# BeagleQ-v31.net
KiCad netlist of a schematic drawn in EAGLE
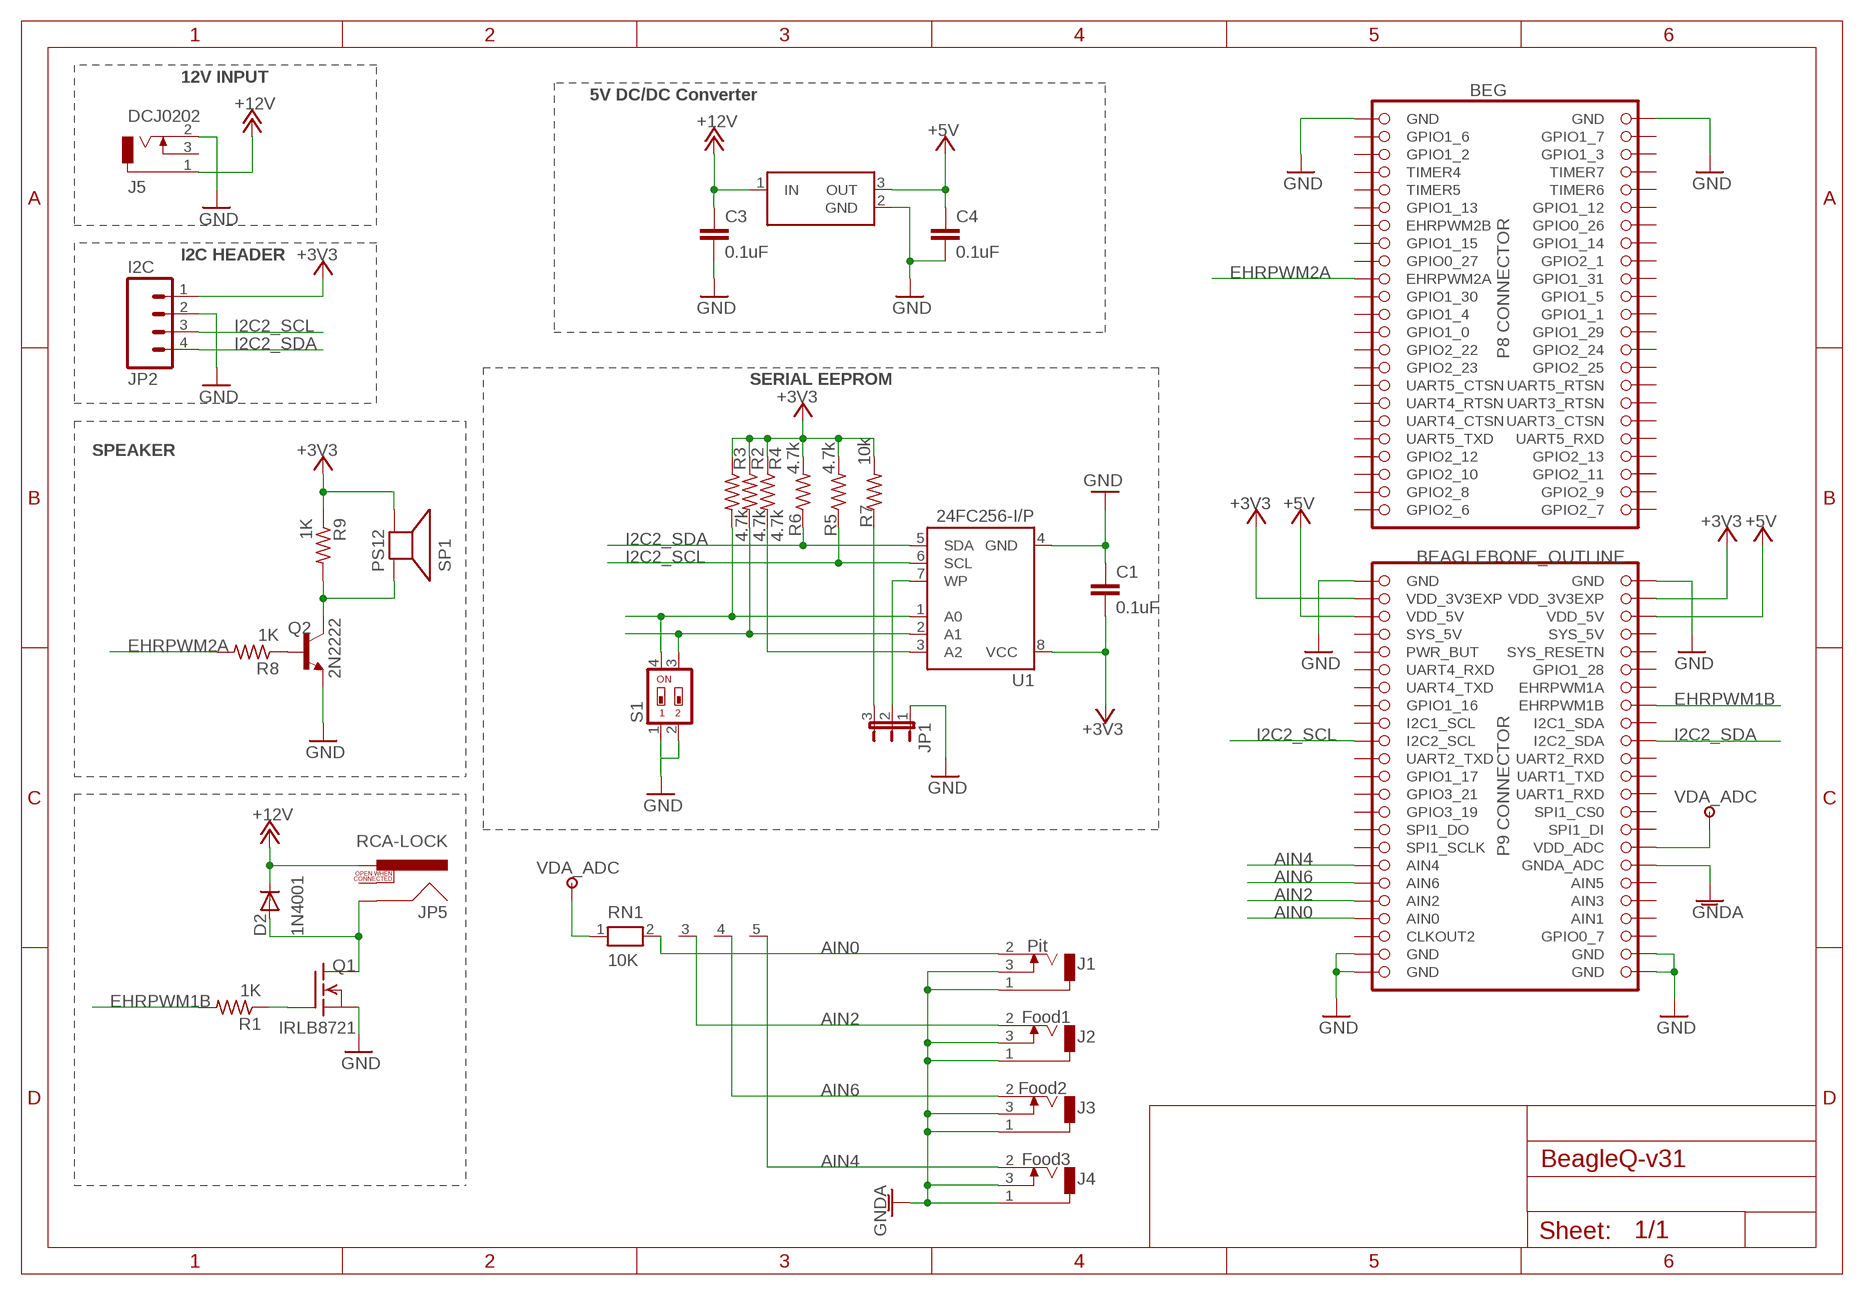
[diagram p0: schematic, sheet 1]

(export (version "E")
  (design (tool "Eeschema 10.0.6"))
  (components
    (comp (ref "BEG")
      (value "BEAGLEBONE_OUTLINE")
      (footprint "eagle-import:BEAGLEBONE_SHIELD")
      (libsource (lib "eagle-import") (part "BEAGLEBONE_OUTLINE"))
    )
    (comp (ref "C1")
      (value "0.1uF")
      (footprint "eagle-import:C2.5-2")
      (libsource (lib "eagle-import") (part "C2.5/2"))
    )
    (comp (ref "C3")
      (value "0.1uF")
      (footprint "eagle-import:C2.5-2")
      (libsource (lib "eagle-import") (part "C2.5/2"))
    )
    (comp (ref "C4")
      (value "0.1uF")
      (footprint "eagle-import:C2.5-2")
      (libsource (lib "eagle-import") (part "C2.5/2"))
    )
    (comp (ref "D2")
      (value "1N4001")
      (footprint "eagle-import:DO41-10")
      (libsource (lib "eagle-import") (part "1N4004"))
    )
    (comp (ref "J1")
      (value "Pit")
      (footprint "eagle-import:MJ-2508N")
      (libsource (lib "eagle-import") (part "MJ-2508N"))
    )
    (comp (ref "J2")
      (value "Food1")
      (footprint "eagle-import:MJ-2508N")
      (libsource (lib "eagle-import") (part "MJ-2508N"))
    )
    (comp (ref "J3")
      (value "Food2")
      (footprint "eagle-import:MJ-2508N")
      (libsource (lib "eagle-import") (part "MJ-2508N"))
    )
    (comp (ref "J4")
      (value "Food3")
      (footprint "eagle-import:MJ-2508N")
      (libsource (lib "eagle-import") (part "MJ-2508N"))
    )
    (comp (ref "J5")
      (value "DCJ0202")
      (footprint "eagle-import:DCJ0202")
      (libsource (lib "eagle-import") (part "DCJ0202"))
    )
    (comp (ref "JP1")
      (value "WP")
      (footprint "eagle-import:JP2")
      (libsource (lib "eagle-import") (part "JP2E"))
    )
    (comp (ref "JP2")
      (value "I2C")
      (footprint "eagle-import:1X04")
      (libsource (lib "eagle-import") (part "M04PTH"))
    )
    (comp (ref "JP5")
      (value "RCA-LOCK")
      (footprint "eagle-import:RCA_LOCK")
      (libsource (lib "eagle-import") (part "RCA-LOCK"))
    )
    (comp (ref "Q1")
      (value "IRLB8721")
      (footprint "eagle-import:TO220")
      (libsource (lib "eagle-import") (part "BUZ10"))
    )
    (comp (ref "Q2")
      (value "2N2222")
      (footprint "eagle-import:TO-92")
      (libsource (lib "eagle-import") (part "2N2222"))
    )
    (comp (ref "R1")
      (value "1K")
      (footprint "eagle-import:0207_10")
      (libsource (lib "eagle-import") (part "R-US_0207/10"))
    )
    (comp (ref "R2")
      (value "4.7k")
      (footprint "eagle-import:0207_10")
      (libsource (lib "eagle-import") (part "resistor_R-US_0207/10"))
    )
    (comp (ref "R3")
      (value "4.7k")
      (footprint "eagle-import:0207_10")
      (libsource (lib "eagle-import") (part "resistor_R-US_0207/10"))
    )
    (comp (ref "R4")
      (value "4.7k")
      (footprint "eagle-import:0207_10")
      (libsource (lib "eagle-import") (part "resistor_R-US_0207/10"))
    )
    (comp (ref "R5")
      (value "4.7k")
      (footprint "eagle-import:0207_10")
      (libsource (lib "eagle-import") (part "resistor_R-US_0207/10"))
    )
    (comp (ref "R6")
      (value "4.7k")
      (footprint "eagle-import:0207_10")
      (libsource (lib "eagle-import") (part "resistor_R-US_0207/10"))
    )
    (comp (ref "R7")
      (value "10k")
      (footprint "eagle-import:0207_10")
      (libsource (lib "eagle-import") (part "resistor_R-US_0207/10"))
    )
    (comp (ref "R8")
      (value "1K")
      (footprint "eagle-import:0207_10")
      (libsource (lib "eagle-import") (part "R-US_0207/10"))
    )
    (comp (ref "R9")
      (value "1K")
      (footprint "eagle-import:0207_10")
      (libsource (lib "eagle-import") (part "R-US_0207/10"))
    )
    (comp (ref "RN1")
      (value "10K")
      (footprint "eagle-import:RN-5")
      (libsource (lib "eagle-import") (part "RN04"))
    )
    (comp (ref "S1")
      (value "SWS002")
      (footprint "eagle-import:SMS-002")
      (libsource (lib "eagle-import") (part "SWS002"))
    )
    (comp (ref "SP1")
      (value "PS12")
      (footprint "eagle-import:PS12")
      (libsource (lib "eagle-import") (part "SPEAKER/PS12"))
    )
    (comp (ref "U1")
      (value "24FC256-I/P")
      (footprint "eagle-import:DIL08")
      (fields (field (name "MPN") "AT24C1024BW-SH-B"))
      (libsource (lib "eagle-import") (part "AT24CP"))
    )
    (comp (ref "U2")
      (value "OKI-78SRHZNTL")
      (footprint "eagle-import:OKI-78SR-HZNTL")
      (libsource (lib "eagle-import") (part "OKI-78SRHZNTL"))
    )
  )
  (nets
    (net (code "1") (name "+3V3") (class "Default")
      (node (ref "BEG") (pin "49") (pinfunction "VDD_3V3EXP_49") (pintype "power_in"))
      (node (ref "BEG") (pin "50") (pinfunction "VDD_3V3EXP_50") (pintype "power_in"))
      (node (ref "C1") (pin "2") (pinfunction "2_2") (pintype "passive"))
      (node (ref "JP2") (pin "1") (pinfunction "1_1") (pintype "passive"))
      (node (ref "R2") (pin "1") (pinfunction "1_1") (pintype "passive"))
      (node (ref "R3") (pin "1") (pinfunction "1_1") (pintype "passive"))
      (node (ref "R4") (pin "1") (pinfunction "1_1") (pintype "passive"))
      (node (ref "R5") (pin "2") (pinfunction "2_2") (pintype "passive"))
      (node (ref "R6") (pin "2") (pinfunction "2_2") (pintype "passive"))
      (node (ref "R7") (pin "2") (pinfunction "2_2") (pintype "passive"))
      (node (ref "R9") (pin "1") (pinfunction "1_1") (pintype "passive"))
      (node (ref "SP1") (pin "P$2") (pinfunction "-_P$2") (pintype "passive"))
      (node (ref "U1") (pin "8") (pinfunction "VCC_8") (pintype "power_in"))
    )
    (net (code "2") (name "+5V") (class "Default")
      (node (ref "BEG") (pin "51") (pinfunction "VDD_5V_51") (pintype "power_in"))
      (node (ref "BEG") (pin "52") (pinfunction "VDD_5V_52") (pintype "power_in"))
      (node (ref "C4") (pin "1") (pinfunction "1_1") (pintype "passive"))
      (node (ref "U2") (pin "3") (pinfunction "OUT_3") (pintype "passive"))
    )
    (net (code "3") (name "+12V") (class "Default")
      (node (ref "C3") (pin "1") (pinfunction "1_1") (pintype "passive"))
      (node (ref "D2") (pin "C") (pinfunction "C_C") (pintype "passive"))
      (node (ref "J5") (pin "1") (pinfunction "1_1") (pintype "passive"))
      (node (ref "JP5") (pin "PIN") (pinfunction "PIN_PIN") (pintype "bidirectional"))
      (node (ref "U2") (pin "1") (pinfunction "IN_1") (pintype "passive"))
    )
    (net (code "4") (name "/AIN0") (class "Default")
      (node (ref "BEG") (pin "85") (pinfunction "AIN0_85") (pintype "power_in"))
      (node (ref "J1") (pin "2") (pinfunction "2_2") (pintype "passive"))
      (node (ref "RN1") (pin "2") (pinfunction "2_2") (pintype "passive"))
    )
    (net (code "5") (name "/AIN2") (class "Default")
      (node (ref "BEG") (pin "83") (pinfunction "AIN2_83") (pintype "passive"))
      (node (ref "J2") (pin "2") (pinfunction "2_2") (pintype "passive"))
      (node (ref "RN1") (pin "3") (pinfunction "3_3") (pintype "passive"))
    )
    (net (code "6") (name "/AIN4") (class "Default")
      (node (ref "BEG") (pin "79") (pinfunction "AIN4_79") (pintype "passive"))
      (node (ref "J4") (pin "2") (pinfunction "2_2") (pintype "passive"))
      (node (ref "RN1") (pin "5") (pinfunction "5_5") (pintype "passive"))
    )
    (net (code "7") (name "/AIN6") (class "Default")
      (node (ref "BEG") (pin "81") (pinfunction "AIN6_81") (pintype "passive"))
      (node (ref "J3") (pin "2") (pinfunction "2_2") (pintype "passive"))
      (node (ref "RN1") (pin "4") (pinfunction "4_4") (pintype "passive"))
    )
    (net (code "8") (name "/EHRPWM1B") (class "Default")
      (node (ref "BEG") (pin "62") (pinfunction "EHRPWM1B_62") (pintype "passive"))
      (node (ref "R1") (pin "2") (pinfunction "2_2") (pintype "passive"))
    )
    (net (code "9") (name "/EHRPWM2A") (class "Default")
      (node (ref "BEG") (pin "19") (pinfunction "EHRPWM2A_19") (pintype "passive"))
      (node (ref "R8") (pin "2") (pinfunction "2_2") (pintype "passive"))
    )
    (net (code "10") (name "/I2C2_SCL") (class "Default")
      (node (ref "BEG") (pin "65") (pinfunction "I2C2_SCL_65") (pintype "passive"))
      (node (ref "JP2") (pin "3") (pinfunction "3_3") (pintype "passive"))
      (node (ref "R5") (pin "1") (pinfunction "1_1") (pintype "passive"))
      (node (ref "U1") (pin "6") (pinfunction "SCL_6") (pintype "bidirectional"))
    )
    (net (code "11") (name "/I2C2_SDA") (class "Default")
      (node (ref "BEG") (pin "66") (pinfunction "I2C2_SDA_66") (pintype "passive"))
      (node (ref "JP2") (pin "4") (pinfunction "4_4") (pintype "passive"))
      (node (ref "R6") (pin "1") (pinfunction "1_1") (pintype "passive"))
      (node (ref "U1") (pin "5") (pinfunction "SDA_5") (pintype "bidirectional"))
    )
    (net (code "12") (name "/SYS_5V") (class "Default")
      (node (ref "BEG") (pin "53") (pinfunction "SYS_5V_53") (pintype "power_in"))
    )
    (net (code "13") (name "GND") (class "Default")
      (node (ref "BEG") (pin "1") (pinfunction "GND_1") (pintype "power_in"))
      (node (ref "BEG") (pin "2") (pinfunction "GND_2") (pintype "power_in"))
      (node (ref "BEG") (pin "47") (pinfunction "GND_47") (pintype "power_in"))
      (node (ref "BEG") (pin "48") (pinfunction "GND_48") (pintype "power_in"))
      (node (ref "BEG") (pin "89") (pinfunction "GND_89") (pintype "power_in"))
      (node (ref "BEG") (pin "90") (pinfunction "GND_90") (pintype "power_in"))
      (node (ref "BEG") (pin "91") (pinfunction "GND_91") (pintype "power_in"))
      (node (ref "BEG") (pin "92") (pinfunction "GND_92") (pintype "power_in"))
      (node (ref "C1") (pin "1") (pinfunction "1_1") (pintype "passive"))
      (node (ref "C3") (pin "2") (pinfunction "2_2") (pintype "passive"))
      (node (ref "C4") (pin "2") (pinfunction "2_2") (pintype "passive"))
      (node (ref "J5") (pin "2") (pinfunction "3_2") (pintype "passive"))
      (node (ref "JP1") (pin "1") (pinfunction "1_1") (pintype "passive"))
      (node (ref "JP2") (pin "2") (pinfunction "2_2") (pintype "passive"))
      (node (ref "Q1") (pin "3") (pinfunction "S_3") (pintype "passive"))
      (node (ref "Q1") (pin "4") (pinfunction "S_4") (pintype "passive"))
      (node (ref "Q2") (pin "1") (pinfunction "E_1") (pintype "passive"))
      (node (ref "S1") (pin "1") (pinfunction "1_1") (pintype "passive"))
      (node (ref "S1") (pin "2") (pinfunction "2_2") (pintype "passive"))
      (node (ref "U1") (pin "4") (pinfunction "GND_4") (pintype "power_in"))
      (node (ref "U2") (pin "2") (pinfunction "GND_2") (pintype "passive"))
    )
    (net (code "14") (name "GNDA") (class "Default")
      (node (ref "BEG") (pin "80") (pinfunction "GNDA_ADC_80") (pintype "passive"))
      (node (ref "J1") (pin "1") (pinfunction "1_1") (pintype "passive"))
      (node (ref "J1") (pin "3") (pinfunction "3_3") (pintype "passive"))
      (node (ref "J2") (pin "1") (pinfunction "1_1") (pintype "passive"))
      (node (ref "J2") (pin "3") (pinfunction "3_3") (pintype "passive"))
      (node (ref "J3") (pin "1") (pinfunction "1_1") (pintype "passive"))
      (node (ref "J3") (pin "3") (pinfunction "3_3") (pintype "passive"))
      (node (ref "J4") (pin "1") (pinfunction "1_1") (pintype "passive"))
      (node (ref "J4") (pin "3") (pinfunction "3_3") (pintype "passive"))
    )
    (net (code "15") (name "Net-(JP1-Pad3)") (class "Default")
      (node (ref "JP1") (pin "3") (pinfunction "3_3") (pintype "passive"))
      (node (ref "R7") (pin "1") (pinfunction "1_1") (pintype "passive"))
    )
    (net (code "16") (name "Net-(Q1-D)") (class "Default")
      (node (ref "D2") (pin "A") (pinfunction "A_A") (pintype "passive"))
      (node (ref "JP5") (pin "SHELL") (pinfunction "SHELL_SHELL") (pintype "bidirectional"))
      (node (ref "Q1") (pin "2") (pinfunction "D_2") (pintype "passive"))
    )
    (net (code "17") (name "Net-(Q1-G)") (class "Default")
      (node (ref "Q1") (pin "1") (pinfunction "G_1") (pintype "passive"))
      (node (ref "R1") (pin "1") (pinfunction "1_1") (pintype "passive"))
    )
    (net (code "18") (name "Net-(Q2-B)") (class "Default")
      (node (ref "Q2") (pin "2") (pinfunction "B_2") (pintype "passive"))
      (node (ref "R8") (pin "1") (pinfunction "1_1") (pintype "passive"))
    )
    (net (code "19") (name "Net-(Q2-C)") (class "Default")
      (node (ref "Q2") (pin "3") (pinfunction "C_3") (pintype "passive"))
      (node (ref "R9") (pin "2") (pinfunction "2_2") (pintype "passive"))
      (node (ref "SP1") (pin "P$1") (pinfunction "+_P$1") (pintype "passive"))
    )
    (net (code "20") (name "Net-(U1-A0)") (class "Default")
      (node (ref "R3") (pin "2") (pinfunction "2_2") (pintype "passive"))
      (node (ref "S1") (pin "4") (pinfunction "4_4") (pintype "passive"))
      (node (ref "U1") (pin "1") (pinfunction "A0_1") (pintype "input"))
    )
    (net (code "21") (name "Net-(U1-A1)") (class "Default")
      (node (ref "R2") (pin "2") (pinfunction "2_2") (pintype "passive"))
      (node (ref "S1") (pin "3") (pinfunction "3_3") (pintype "passive"))
      (node (ref "U1") (pin "2") (pinfunction "A1_2") (pintype "input"))
    )
    (net (code "22") (name "Net-(U1-A2)") (class "Default")
      (node (ref "R4") (pin "2") (pinfunction "2_2") (pintype "passive"))
      (node (ref "U1") (pin "3") (pinfunction "A2_3") (pintype "input"))
    )
    (net (code "23") (name "Net-(U1-WP)") (class "Default")
      (node (ref "JP1") (pin "2") (pinfunction "2_2") (pintype "passive"))
      (node (ref "U1") (pin "7") (pinfunction "WP_7") (pintype "input"))
    )
    (net (code "24") (name "VDA_ADC") (class "Default")
      (node (ref "BEG") (pin "78") (pinfunction "VDD_ADC_78") (pintype "passive"))
      (node (ref "RN1") (pin "1") (pinfunction "1_1") (pintype "passive"))
    )
    (net (code "25") (name "unconnected-(BEG-AIN1-Pad86)") (class "Default")
      (node (ref "BEG") (pin "86") (pinfunction "AIN1_86") (pintype "passive"))
    )
    (net (code "26") (name "unconnected-(BEG-AIN3-Pad84)") (class "Default")
      (node (ref "BEG") (pin "84") (pinfunction "AIN3_84") (pintype "passive"))
    )
    (net (code "27") (name "unconnected-(BEG-AIN5-Pad82)") (class "Default")
      (node (ref "BEG") (pin "82") (pinfunction "AIN5_82") (pintype "passive"))
    )
    (net (code "28") (name "unconnected-(BEG-CLKOUT2-Pad87)") (class "Default")
      (node (ref "BEG") (pin "87") (pinfunction "CLKOUT2_87") (pintype "input"))
    )
    (net (code "29") (name "unconnected-(BEG-EHRPWM1A-Pad60)") (class "Default")
      (node (ref "BEG") (pin "60") (pinfunction "EHRPWM1A_60") (pintype "passive"))
    )
    (net (code "30") (name "unconnected-(BEG-EHRPWM2B-Pad13)") (class "Default")
      (node (ref "BEG") (pin "13") (pinfunction "EHRPWM2B_13") (pintype "passive"))
    )
    (net (code "31") (name "unconnected-(BEG-GPIO0_7-Pad88)") (class "Default")
      (node (ref "BEG") (pin "88") (pinfunction "GPIO0_7_88") (pintype "passive"))
    )
    (net (code "32") (name "unconnected-(BEG-GPIO0_26-Pad14)") (class "Default")
      (node (ref "BEG") (pin "14") (pinfunction "GPIO0_26_14") (pintype "passive"))
    )
    (net (code "33") (name "unconnected-(BEG-GPIO0_27-Pad17)") (class "Default")
      (node (ref "BEG") (pin "17") (pinfunction "GPIO0_27_17") (pintype "passive"))
    )
    (net (code "34") (name "unconnected-(BEG-GPIO1_0-Pad25)") (class "Default")
      (node (ref "BEG") (pin "25") (pinfunction "GPIO1_0_25") (pintype "passive"))
    )
    (net (code "35") (name "unconnected-(BEG-GPIO1_1-Pad24)") (class "Default")
      (node (ref "BEG") (pin "24") (pinfunction "GPIO1_1_24") (pintype "passive"))
    )
    (net (code "36") (name "unconnected-(BEG-GPIO1_2-Pad5)") (class "Default")
      (node (ref "BEG") (pin "5") (pinfunction "GPIO1_2_5") (pintype "passive"))
    )
    (net (code "37") (name "unconnected-(BEG-GPIO1_3-Pad6)") (class "Default")
      (node (ref "BEG") (pin "6") (pinfunction "GPIO1_3_6") (pintype "passive"))
    )
    (net (code "38") (name "unconnected-(BEG-GPIO1_4-Pad23)") (class "Default")
      (node (ref "BEG") (pin "23") (pinfunction "GPIO1_4_23") (pintype "passive"))
    )
    (net (code "39") (name "unconnected-(BEG-GPIO1_5-Pad22)") (class "Default")
      (node (ref "BEG") (pin "22") (pinfunction "GPIO1_5_22") (pintype "passive"))
    )
    (net (code "40") (name "unconnected-(BEG-GPIO1_6-Pad3)") (class "Default")
      (node (ref "BEG") (pin "3") (pinfunction "GPIO1_6_3") (pintype "passive"))
    )
    (net (code "41") (name "unconnected-(BEG-GPIO1_7-Pad4)") (class "Default")
      (node (ref "BEG") (pin "4") (pinfunction "GPIO1_7_4") (pintype "passive"))
    )
    (net (code "42") (name "unconnected-(BEG-GPIO1_12-Pad12)") (class "Default")
      (node (ref "BEG") (pin "12") (pinfunction "GPIO1_12_12") (pintype "passive"))
    )
    (net (code "43") (name "unconnected-(BEG-GPIO1_13-Pad11)") (class "Default")
      (node (ref "BEG") (pin "11") (pinfunction "GPIO1_13_11") (pintype "passive"))
    )
    (net (code "44") (name "unconnected-(BEG-GPIO1_14-Pad16)") (class "Default")
      (node (ref "BEG") (pin "16") (pinfunction "GPIO1_14_16") (pintype "passive"))
    )
    (net (code "45") (name "unconnected-(BEG-GPIO1_15-Pad15)") (class "Default")
      (node (ref "BEG") (pin "15") (pinfunction "GPIO1_15_15") (pintype "passive"))
    )
    (net (code "46") (name "unconnected-(BEG-GPIO1_16-Pad61)") (class "Default")
      (node (ref "BEG") (pin "61") (pinfunction "GPIO1_16_61") (pintype "passive"))
    )
    (net (code "47") (name "unconnected-(BEG-GPIO1_17-Pad69)") (class "Default")
      (node (ref "BEG") (pin "69") (pinfunction "GPIO1_17_69") (pintype "passive"))
    )
    (net (code "48") (name "unconnected-(BEG-GPIO1_28-Pad58)") (class "Default")
      (node (ref "BEG") (pin "58") (pinfunction "GPIO1_28_58") (pintype "passive"))
    )
    (net (code "49") (name "unconnected-(BEG-GPIO1_29-Pad26)") (class "Default")
      (node (ref "BEG") (pin "26") (pinfunction "GPIO1_29_26") (pintype "passive"))
    )
    (net (code "50") (name "unconnected-(BEG-GPIO1_30-Pad21)") (class "Default")
      (node (ref "BEG") (pin "21") (pinfunction "GPIO1_30_21") (pintype "passive"))
    )
    (net (code "51") (name "unconnected-(BEG-GPIO1_31-Pad20)") (class "Default")
      (node (ref "BEG") (pin "20") (pinfunction "GPIO1_31_20") (pintype "passive"))
    )
    (net (code "52") (name "unconnected-(BEG-GPIO2_1-Pad18)") (class "Default")
      (node (ref "BEG") (pin "18") (pinfunction "GPIO2_1_18") (pintype "passive"))
    )
    (net (code "53") (name "unconnected-(BEG-GPIO2_6-Pad45)") (class "Default")
      (node (ref "BEG") (pin "45") (pinfunction "GPIO2_6_45") (pintype "passive"))
    )
    (net (code "54") (name "unconnected-(BEG-GPIO2_7-Pad46)") (class "Default")
      (node (ref "BEG") (pin "46") (pinfunction "GPIO2_7_46") (pintype "passive"))
    )
    (net (code "55") (name "unconnected-(BEG-GPIO2_8-Pad43)") (class "Default")
      (node (ref "BEG") (pin "43") (pinfunction "GPIO2_8_43") (pintype "passive"))
    )
    (net (code "56") (name "unconnected-(BEG-GPIO2_9-Pad44)") (class "Default")
      (node (ref "BEG") (pin "44") (pinfunction "GPIO2_9_44") (pintype "passive"))
    )
    (net (code "57") (name "unconnected-(BEG-GPIO2_10-Pad41)") (class "Default")
      (node (ref "BEG") (pin "41") (pinfunction "GPIO2_10_41") (pintype "passive"))
    )
    (net (code "58") (name "unconnected-(BEG-GPIO2_11-Pad42)") (class "Default")
      (node (ref "BEG") (pin "42") (pinfunction "GPIO2_11_42") (pintype "passive"))
    )
    (net (code "59") (name "unconnected-(BEG-GPIO2_12-Pad39)") (class "Default")
      (node (ref "BEG") (pin "39") (pinfunction "GPIO2_12_39") (pintype "passive"))
    )
    (net (code "60") (name "unconnected-(BEG-GPIO2_13-Pad40)") (class "Default")
      (node (ref "BEG") (pin "40") (pinfunction "GPIO2_13_40") (pintype "passive"))
    )
    (net (code "61") (name "unconnected-(BEG-GPIO2_22-Pad27)") (class "Default")
      (node (ref "BEG") (pin "27") (pinfunction "GPIO2_22_27") (pintype "passive"))
    )
    (net (code "62") (name "unconnected-(BEG-GPIO2_23-Pad29)") (class "Default")
      (node (ref "BEG") (pin "29") (pinfunction "GPIO2_23_29") (pintype "passive"))
    )
    (net (code "63") (name "unconnected-(BEG-GPIO2_24-Pad28)") (class "Default")
      (node (ref "BEG") (pin "28") (pinfunction "GPIO2_24_28") (pintype "passive"))
    )
    (net (code "64") (name "unconnected-(BEG-GPIO2_25-Pad30)") (class "Default")
      (node (ref "BEG") (pin "30") (pinfunction "GPIO2_25_30") (pintype "passive"))
    )
    (net (code "65") (name "unconnected-(BEG-GPIO3_19-Pad73)") (class "Default")
      (node (ref "BEG") (pin "73") (pinfunction "GPIO3_19_73") (pintype "passive"))
    )
    (net (code "66") (name "unconnected-(BEG-GPIO3_21-Pad71)") (class "Default")
      (node (ref "BEG") (pin "71") (pinfunction "GPIO3_21_71") (pintype "passive"))
    )
    (net (code "67") (name "unconnected-(BEG-I2C1_SCL-Pad63)") (class "Default")
      (node (ref "BEG") (pin "63") (pinfunction "I2C1_SCL_63") (pintype "passive"))
    )
    (net (code "68") (name "unconnected-(BEG-I2C1_SDA-Pad64)") (class "Default")
      (node (ref "BEG") (pin "64") (pinfunction "I2C1_SDA_64") (pintype "passive"))
    )
    (net (code "69") (name "unconnected-(BEG-PWR_BUT-Pad55)") (class "Default")
      (node (ref "BEG") (pin "55") (pinfunction "PWR_BUT_55") (pintype "passive"))
    )
    (net (code "70") (name "unconnected-(BEG-SPI1_CS0-Pad74)") (class "Default")
      (node (ref "BEG") (pin "74") (pinfunction "SPI1_CS0_74") (pintype "passive"))
    )
    (net (code "71") (name "unconnected-(BEG-SPI1_DI-Pad76)") (class "Default")
      (node (ref "BEG") (pin "76") (pinfunction "SPI1_DI_76") (pintype "passive"))
    )
    (net (code "72") (name "unconnected-(BEG-SPI1_DO-Pad75)") (class "Default")
      (node (ref "BEG") (pin "75") (pinfunction "SPI1_DO_75") (pintype "passive"))
    )
    (net (code "73") (name "unconnected-(BEG-SPI1_SCLK-Pad77)") (class "Default")
      (node (ref "BEG") (pin "77") (pinfunction "SPI1_SCLK_77") (pintype "passive"))
    )
    (net (code "74") (name "unconnected-(BEG-SYS_5V-Pad54)") (class "Default")
      (node (ref "BEG") (pin "54") (pinfunction "SYS_5V_54") (pintype "passive"))
    )
    (net (code "75") (name "unconnected-(BEG-SYS_RESETN-Pad56)") (class "Default")
      (node (ref "BEG") (pin "56") (pinfunction "SYS_RESETN_56") (pintype "passive"))
    )
    (net (code "76") (name "unconnected-(BEG-TIMER4-Pad7)") (class "Default")
      (node (ref "BEG") (pin "7") (pinfunction "TIMER4_7") (pintype "passive"))
    )
    (net (code "77") (name "unconnected-(BEG-TIMER5-Pad9)") (class "Default")
      (node (ref "BEG") (pin "9") (pinfunction "TIMER5_9") (pintype "passive"))
    )
    (net (code "78") (name "unconnected-(BEG-TIMER6-Pad10)") (class "Default")
      (node (ref "BEG") (pin "10") (pinfunction "TIMER6_10") (pintype "passive"))
    )
    (net (code "79") (name "unconnected-(BEG-TIMER7-Pad8)") (class "Default")
      (node (ref "BEG") (pin "8") (pinfunction "TIMER7_8") (pintype "passive"))
    )
    (net (code "80") (name "unconnected-(BEG-UART1_RXD-Pad72)") (class "Default")
      (node (ref "BEG") (pin "72") (pinfunction "UART1_RXD_72") (pintype "passive"))
    )
    (net (code "81") (name "unconnected-(BEG-UART1_TXD-Pad70)") (class "Default")
      (node (ref "BEG") (pin "70") (pinfunction "UART1_TXD_70") (pintype "passive"))
    )
    (net (code "82") (name "unconnected-(BEG-UART2_RXD-Pad68)") (class "Default")
      (node (ref "BEG") (pin "68") (pinfunction "UART2_RXD_68") (pintype "passive"))
    )
    (net (code "83") (name "unconnected-(BEG-UART2_TXD-Pad67)") (class "Default")
      (node (ref "BEG") (pin "67") (pinfunction "UART2_TXD_67") (pintype "passive"))
    )
    (net (code "84") (name "unconnected-(BEG-UART3_CTSN-Pad36)") (class "Default")
      (node (ref "BEG") (pin "36") (pinfunction "UART3_CTSN_36") (pintype "passive"))
    )
    (net (code "85") (name "unconnected-(BEG-UART3_RTSN-Pad34)") (class "Default")
      (node (ref "BEG") (pin "34") (pinfunction "UART3_RTSN_34") (pintype "passive"))
    )
    (net (code "86") (name "unconnected-(BEG-UART4_CTSN-Pad35)") (class "Default")
      (node (ref "BEG") (pin "35") (pinfunction "UART4_CTSN_35") (pintype "passive"))
    )
    (net (code "87") (name "unconnected-(BEG-UART4_RTSN-Pad33)") (class "Default")
      (node (ref "BEG") (pin "33") (pinfunction "UART4_RTSN_33") (pintype "passive"))
    )
    (net (code "88") (name "unconnected-(BEG-UART4_RXD-Pad57)") (class "Default")
      (node (ref "BEG") (pin "57") (pinfunction "UART4_RXD_57") (pintype "passive"))
    )
    (net (code "89") (name "unconnected-(BEG-UART4_TXD-Pad59)") (class "Default")
      (node (ref "BEG") (pin "59") (pinfunction "UART4_TXD_59") (pintype "passive"))
    )
    (net (code "90") (name "unconnected-(BEG-UART5_CTSN-Pad31)") (class "Default")
      (node (ref "BEG") (pin "31") (pinfunction "UART5_CTSN_31") (pintype "passive"))
    )
    (net (code "91") (name "unconnected-(BEG-UART5_RTSN-Pad32)") (class "Default")
      (node (ref "BEG") (pin "32") (pinfunction "UART5_RTSN_32") (pintype "passive"))
    )
    (net (code "92") (name "unconnected-(BEG-UART5_RXD-Pad38)") (class "Default")
      (node (ref "BEG") (pin "38") (pinfunction "UART5_RXD_38") (pintype "passive"))
    )
    (net (code "93") (name "unconnected-(BEG-UART5_TXD-Pad37)") (class "Default")
      (node (ref "BEG") (pin "37") (pinfunction "UART5_TXD_37") (pintype "passive"))
    )
    (net (code "94") (name "unconnected-(J5-2-Pad3)") (class "Default")
      (node (ref "J5") (pin "3") (pinfunction "2_3") (pintype "passive"))
    )
    (net (code "95") (name "unconnected-(JP5-PadSWITCH)") (class "Default")
      (node (ref "JP5") (pin "SWITCH") (pinfunction "SWITCH_SWITCH") (pintype "bidirectional"))
    )
  )
)
